# untitled.net
KiCad netlist of a schematic drawn in EAGLE
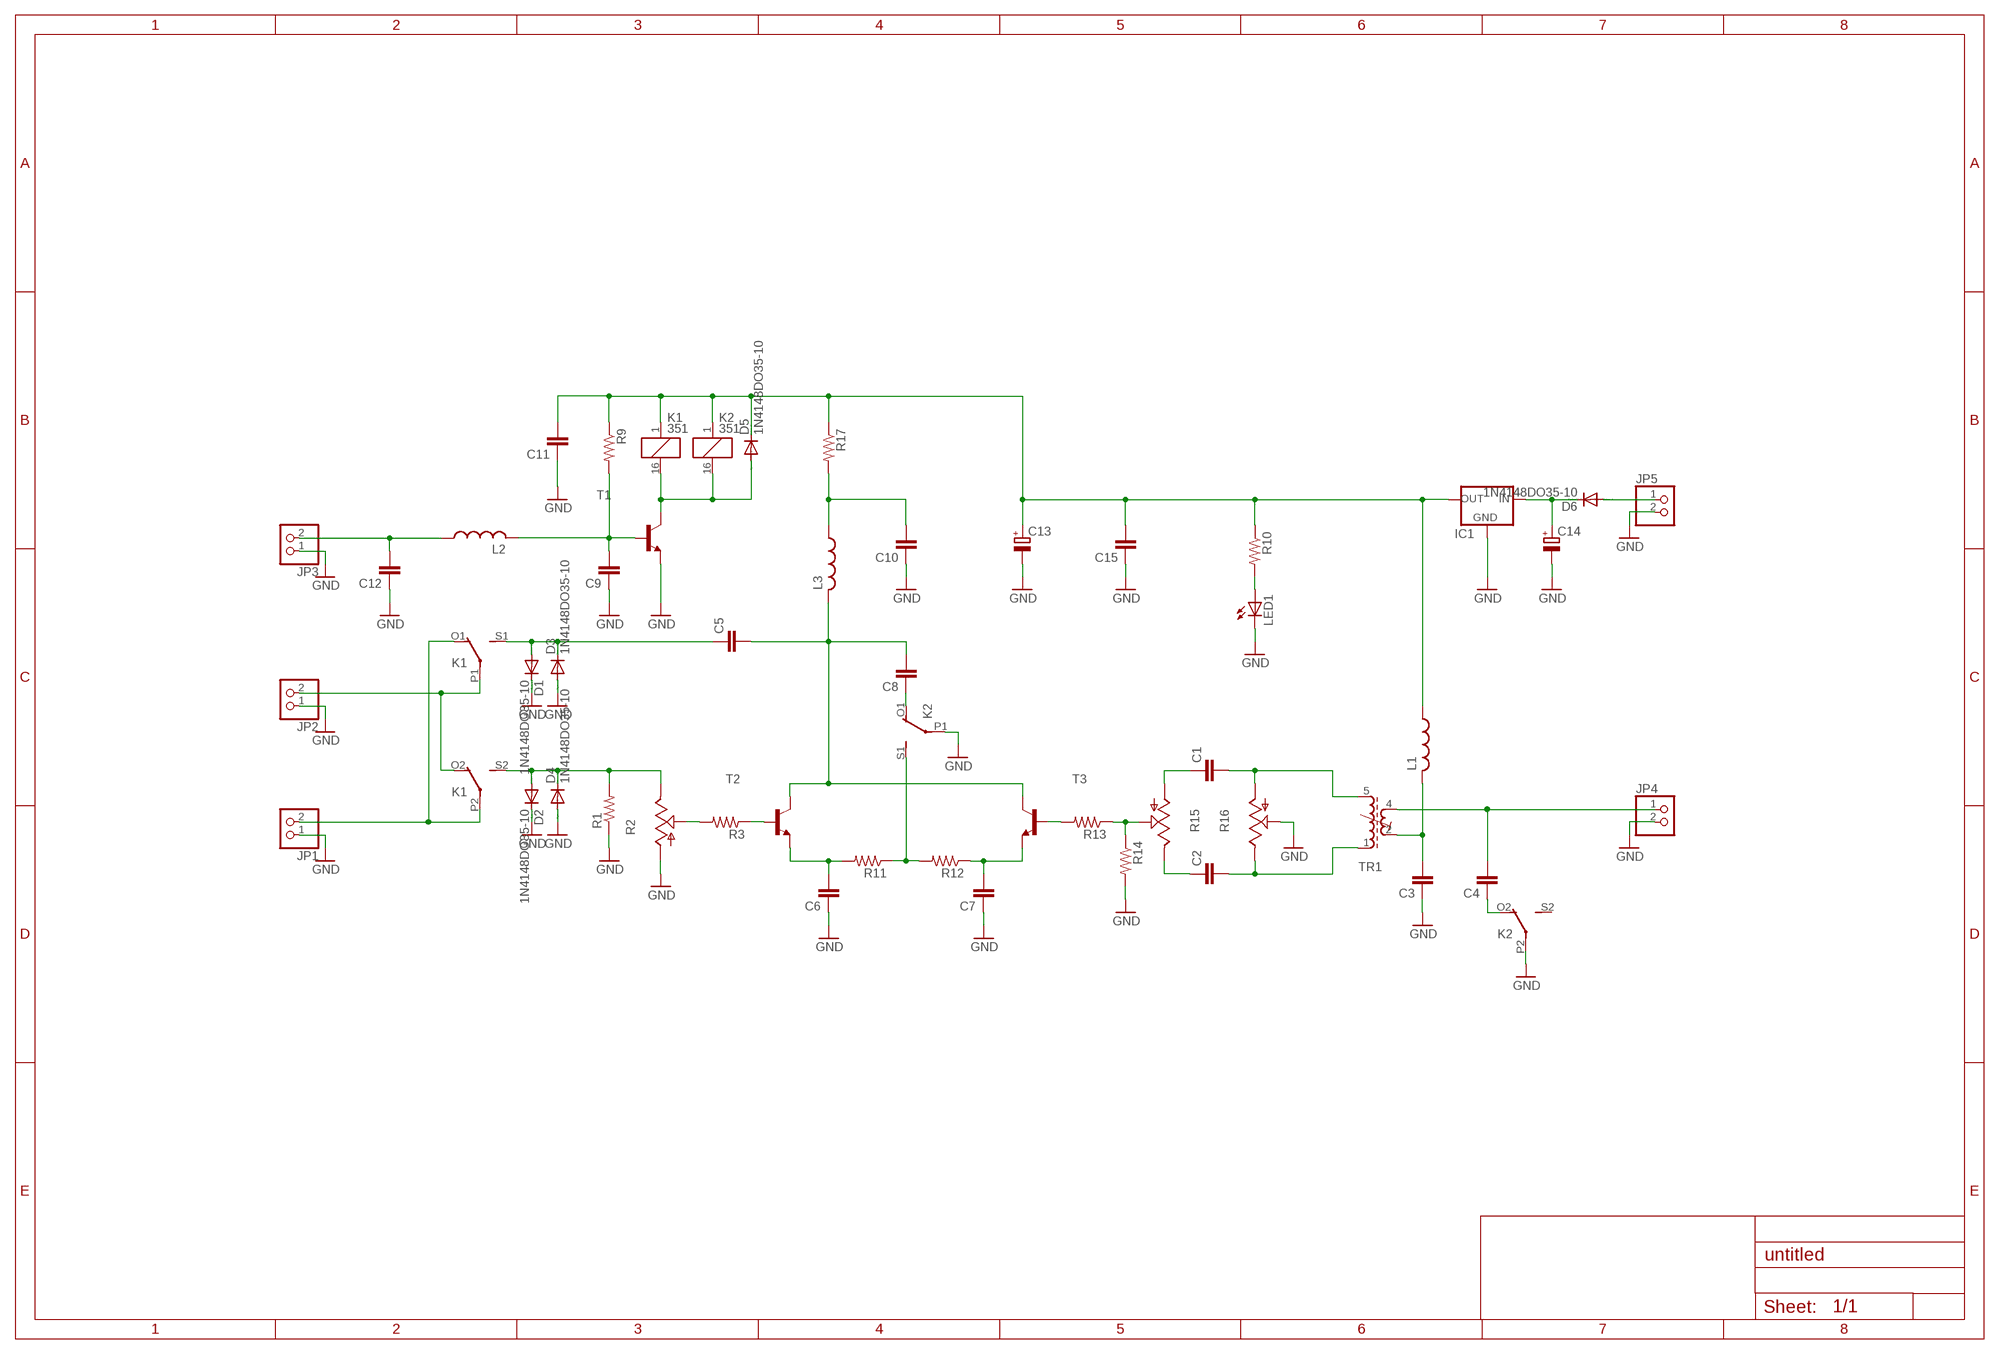
[diagram p0: schematic, sheet 1]

(export (version "E")
  (design (tool "Eeschema 10.0.6"))
  (components
    (comp (ref "C1")
      (value "C-EU050-025X075")
      (footprint "eagle-import:C050-025X075")
      (libsource (lib "eagle-import") (part "C-EU050-025X075"))
    )
    (comp (ref "C2")
      (value "C-EU050-025X075")
      (footprint "eagle-import:C050-025X075")
      (libsource (lib "eagle-import") (part "C-EU050-025X075"))
    )
    (comp (ref "C3")
      (value "C-EU050-025X075")
      (footprint "eagle-import:C050-025X075")
      (libsource (lib "eagle-import") (part "C-EU050-025X075"))
    )
    (comp (ref "C4")
      (value "C-EU050-025X075")
      (footprint "eagle-import:C050-025X075")
      (libsource (lib "eagle-import") (part "C-EU050-025X075"))
    )
    (comp (ref "C5")
      (value "C-EU050-025X075")
      (footprint "eagle-import:C050-025X075")
      (libsource (lib "eagle-import") (part "C-EU050-025X075"))
    )
    (comp (ref "C6")
      (value "C-EU050-025X075")
      (footprint "eagle-import:C050-025X075")
      (libsource (lib "eagle-import") (part "C-EU050-025X075"))
    )
    (comp (ref "C7")
      (value "C-EU050-025X075")
      (footprint "eagle-import:C050-025X075")
      (libsource (lib "eagle-import") (part "C-EU050-025X075"))
    )
    (comp (ref "C8")
      (value "C-EU050-025X075")
      (footprint "eagle-import:C050-025X075")
      (libsource (lib "eagle-import") (part "C-EU050-025X075"))
    )
    (comp (ref "C9")
      (value "C-EU050-025X075")
      (footprint "eagle-import:C050-025X075")
      (libsource (lib "eagle-import") (part "C-EU050-025X075"))
    )
    (comp (ref "C10")
      (value "C-EU050-025X075")
      (footprint "eagle-import:C050-025X075")
      (libsource (lib "eagle-import") (part "C-EU050-025X075"))
    )
    (comp (ref "C11")
      (value "C-EU050-025X075")
      (footprint "eagle-import:C050-025X075")
      (libsource (lib "eagle-import") (part "C-EU050-025X075"))
    )
    (comp (ref "C12")
      (value "C-EU050-025X075")
      (footprint "eagle-import:C050-025X075")
      (libsource (lib "eagle-import") (part "C-EU050-025X075"))
    )
    (comp (ref "C13")
      (value "CPOL-EUE2.5-5")
      (footprint "eagle-import:E2,5-5")
      (libsource (lib "eagle-import") (part "CPOL-EUE2.5-5"))
    )
    (comp (ref "C14")
      (value "CPOL-EUE2.5-5")
      (footprint "eagle-import:E2,5-5")
      (libsource (lib "eagle-import") (part "CPOL-EUE2.5-5"))
    )
    (comp (ref "C15")
      (value "C-EU050-025X075")
      (footprint "eagle-import:C050-025X075")
      (libsource (lib "eagle-import") (part "C-EU050-025X075"))
    )
    (comp (ref "D1")
      (value "1N4148DO35-10")
      (footprint "eagle-import:DO35-10")
      (libsource (lib "eagle-import") (part "1N4148DO35-10"))
    )
    (comp (ref "D2")
      (value "1N4148DO35-10")
      (footprint "eagle-import:DO35-10")
      (libsource (lib "eagle-import") (part "1N4148DO35-10"))
    )
    (comp (ref "D3")
      (value "1N4148DO35-10")
      (footprint "eagle-import:DO35-10")
      (libsource (lib "eagle-import") (part "1N4148DO35-10"))
    )
    (comp (ref "D4")
      (value "1N4148DO35-10")
      (footprint "eagle-import:DO35-10")
      (libsource (lib "eagle-import") (part "1N4148DO35-10"))
    )
    (comp (ref "D5")
      (value "1N4148DO35-10")
      (footprint "eagle-import:DO35-10")
      (libsource (lib "eagle-import") (part "1N4148DO35-10"))
    )
    (comp (ref "D6")
      (value "1N4148DO35-10")
      (footprint "eagle-import:DO35-10")
      (libsource (lib "eagle-import") (part "1N4148DO35-10"))
    )
    (comp (ref "IC1")
      (value "78XXS")
      (footprint "eagle-import:78XXS")
      (libsource (lib "eagle-import") (part "78XXS"))
    )
    (comp (ref "JP1")
      (value "PINHD-1X2")
      (footprint "eagle-import:1X02")
      (libsource (lib "eagle-import") (part "PINHD-1X2"))
    )
    (comp (ref "JP2")
      (value "PINHD-1X2")
      (footprint "eagle-import:1X02")
      (libsource (lib "eagle-import") (part "PINHD-1X2"))
    )
    (comp (ref "JP3")
      (value "PINHD-1X2")
      (footprint "eagle-import:1X02")
      (libsource (lib "eagle-import") (part "PINHD-1X2"))
    )
    (comp (ref "JP4")
      (value "PINHD-1X2")
      (footprint "eagle-import:1X02")
      (libsource (lib "eagle-import") (part "PINHD-1X2"))
    )
    (comp (ref "JP5")
      (value "PINHD-1X2")
      (footprint "eagle-import:1X02")
      (libsource (lib "eagle-import") (part "PINHD-1X2"))
    )
    (comp (ref "K1")
      (value "351")
      (footprint "eagle-import:351")
      (libsource (lib "eagle-import") (part "351"))
    )
    (comp (ref "K2")
      (value "351")
      (footprint "eagle-import:351")
      (libsource (lib "eagle-import") (part "351"))
    )
    (comp (ref "L1")
      (value "L-US0207/7")
      (footprint "eagle-import:0207_7")
      (libsource (lib "eagle-import") (part "L-US0207/7"))
    )
    (comp (ref "L2")
      (value "L-US0207/7")
      (footprint "eagle-import:0207_7")
      (libsource (lib "eagle-import") (part "L-US0207/7"))
    )
    (comp (ref "L3")
      (value "L-US0207/7")
      (footprint "eagle-import:0207_7")
      (libsource (lib "eagle-import") (part "L-US0207/7"))
    )
    (comp (ref "LED1")
      (value "LED3MM")
      (footprint "eagle-import:LED3MM")
      (libsource (lib "eagle-import") (part "LED3MM"))
    )
    (comp (ref "R1")
      (value "R-US_0309/12")
      (footprint "eagle-import:0309_12")
      (libsource (lib "eagle-import") (part "R-US_0309/12"))
    )
    (comp (ref "R2")
      (value "TRIM_US-CIP20C-6MM")
      (footprint "eagle-import:CIP20C-6MM")
      (libsource (lib "eagle-import") (part "TRIM_US-CIP20C-6MM"))
    )
    (comp (ref "R3")
      (value "R-US_0207/7")
      (footprint "eagle-import:0207_7")
      (libsource (lib "eagle-import") (part "R-US_0207/7"))
    )
    (comp (ref "R9")
      (value "R-US_0207/7")
      (footprint "eagle-import:0207_7")
      (libsource (lib "eagle-import") (part "R-US_0207/7"))
    )
    (comp (ref "R10")
      (value "R-US_0207/7")
      (footprint "eagle-import:0207_7")
      (libsource (lib "eagle-import") (part "R-US_0207/7"))
    )
    (comp (ref "R11")
      (value "R-US_0207/7")
      (footprint "eagle-import:0207_7")
      (libsource (lib "eagle-import") (part "R-US_0207/7"))
    )
    (comp (ref "R12")
      (value "R-US_0207/7")
      (footprint "eagle-import:0207_7")
      (libsource (lib "eagle-import") (part "R-US_0207/7"))
    )
    (comp (ref "R13")
      (value "R-US_0207/7")
      (footprint "eagle-import:0207_7")
      (libsource (lib "eagle-import") (part "R-US_0207/7"))
    )
    (comp (ref "R14")
      (value "R-US_0207/7")
      (footprint "eagle-import:0207_7")
      (libsource (lib "eagle-import") (part "R-US_0207/7"))
    )
    (comp (ref "R15")
      (value "TRIM_US-CIP20C-6MM")
      (footprint "eagle-import:CIP20C-6MM")
      (libsource (lib "eagle-import") (part "TRIM_US-CIP20C-6MM"))
    )
    (comp (ref "R16")
      (value "TRIM_US-CIP20C-6MM")
      (footprint "eagle-import:CIP20C-6MM")
      (libsource (lib "eagle-import") (part "TRIM_US-CIP20C-6MM"))
    )
    (comp (ref "R17")
      (value "R-US_0207/7")
      (footprint "eagle-import:0207_7")
      (libsource (lib "eagle-import") (part "R-US_0207/7"))
    )
    (comp (ref "T1")
      (value "-NPN-TO92-EBC")
      (footprint "eagle-import:TO92-EBC")
      (libsource (lib "eagle-import") (part "-NPN-TO92-EBC"))
    )
    (comp (ref "T2")
      (value "-NPN-TO92-EBC")
      (footprint "eagle-import:TO92-EBC")
      (libsource (lib "eagle-import") (part "-NPN-TO92-EBC"))
    )
    (comp (ref "T3")
      (value "-NPN-TO92-EBC")
      (footprint "eagle-import:TO92-EBC")
      (libsource (lib "eagle-import") (part "-NPN-TO92-EBC"))
    )
    (comp (ref "TR1")
      (value "71-4-1524")
      (footprint "eagle-import:71-5")
      (libsource (lib "eagle-import") (part "71-4-1524"))
    )
  )
  (nets
    (net (code "1") (name "GND") (class "Default")
      (node (ref "C10") (pin "1") (pinfunction "1_1") (pintype "passive"))
      (node (ref "C11") (pin "1") (pinfunction "1_1") (pintype "passive"))
      (node (ref "C12") (pin "1") (pinfunction "1_1") (pintype "passive"))
      (node (ref "C13") (pin "-") (pinfunction "-_-") (pintype "passive"))
      (node (ref "C14") (pin "-") (pinfunction "-_-") (pintype "passive"))
      (node (ref "C15") (pin "1") (pinfunction "1_1") (pintype "passive"))
      (node (ref "C3") (pin "1") (pinfunction "1_1") (pintype "passive"))
      (node (ref "C6") (pin "1") (pinfunction "1_1") (pintype "passive"))
      (node (ref "C7") (pin "1") (pinfunction "1_1") (pintype "passive"))
      (node (ref "C9") (pin "1") (pinfunction "1_1") (pintype "passive"))
      (node (ref "D1") (pin "C") (pinfunction "C_C") (pintype "passive"))
      (node (ref "D2") (pin "C") (pinfunction "C_C") (pintype "passive"))
      (node (ref "D3") (pin "A") (pinfunction "A_A") (pintype "passive"))
      (node (ref "D4") (pin "A") (pinfunction "A_A") (pintype "passive"))
      (node (ref "IC1") (pin "GND") (pinfunction "GND_GND") (pintype "input"))
      (node (ref "JP1") (pin "1") (pinfunction "1_1") (pintype "passive"))
      (node (ref "JP2") (pin "1") (pinfunction "1_1") (pintype "passive"))
      (node (ref "JP3") (pin "1") (pinfunction "1_1") (pintype "passive"))
      (node (ref "JP4") (pin "2") (pinfunction "2_2") (pintype "passive"))
      (node (ref "JP5") (pin "2") (pinfunction "2_2") (pintype "passive"))
      (node (ref "K2") (pin "P1") (pinfunction "P_P1") (pintype "passive"))
      (node (ref "K2") (pin "P2") (pinfunction "P_P2") (pintype "passive"))
      (node (ref "LED1") (pin "K") (pinfunction "C_K") (pintype "passive"))
      (node (ref "R1") (pin "1") (pinfunction "1_1") (pintype "passive"))
      (node (ref "R14") (pin "2") (pinfunction "2_2") (pintype "passive"))
      (node (ref "R16") (pin "S") (pinfunction "S_S") (pintype "passive"))
      (node (ref "R2") (pin "A") (pinfunction "A_A") (pintype "passive"))
      (node (ref "T1") (pin "E") (pinfunction "E_E") (pintype "passive"))
    )
    (net (code "2") (name "Net-(C1-Pad1)") (class "Default")
      (node (ref "C1") (pin "1") (pinfunction "1_1") (pintype "passive"))
      (node (ref "R15") (pin "A") (pinfunction "A_A") (pintype "passive"))
    )
    (net (code "3") (name "Net-(C2-Pad1)") (class "Default")
      (node (ref "C2") (pin "1") (pinfunction "1_1") (pintype "passive"))
      (node (ref "R15") (pin "E") (pinfunction "E_E") (pintype "passive"))
    )
    (net (code "4") (name "Net-(C5-Pad2)") (class "Default")
      (node (ref "C5") (pin "2") (pinfunction "2_2") (pintype "passive"))
      (node (ref "C8") (pin "2") (pinfunction "2_2") (pintype "passive"))
      (node (ref "L3") (pin "2") (pinfunction "2_2") (pintype "passive"))
      (node (ref "T2") (pin "C") (pinfunction "C_C") (pintype "passive"))
      (node (ref "T3") (pin "C") (pinfunction "C_C") (pintype "passive"))
    )
    (net (code "5") (name "Net-(C6-Pad2)") (class "Default")
      (node (ref "C6") (pin "2") (pinfunction "2_2") (pintype "passive"))
      (node (ref "R11") (pin "2") (pinfunction "2_2") (pintype "passive"))
      (node (ref "T2") (pin "E") (pinfunction "E_E") (pintype "passive"))
    )
    (net (code "6") (name "Net-(C7-Pad2)") (class "Default")
      (node (ref "C7") (pin "2") (pinfunction "2_2") (pintype "passive"))
      (node (ref "R12") (pin "1") (pinfunction "1_1") (pintype "passive"))
      (node (ref "T3") (pin "E") (pinfunction "E_E") (pintype "passive"))
    )
    (net (code "7") (name "Net-(C9-Pad2)") (class "Default")
      (node (ref "C9") (pin "2") (pinfunction "2_2") (pintype "passive"))
      (node (ref "L2") (pin "2") (pinfunction "2_2") (pintype "passive"))
      (node (ref "R9") (pin "2") (pinfunction "2_2") (pintype "passive"))
      (node (ref "T1") (pin "B") (pinfunction "B_B") (pintype "passive"))
    )
    (net (code "8") (name "Net-(C10-Pad2)") (class "Default")
      (node (ref "C10") (pin "2") (pinfunction "2_2") (pintype "passive"))
      (node (ref "L3") (pin "1") (pinfunction "1_1") (pintype "passive"))
      (node (ref "R17") (pin "2") (pinfunction "2_2") (pintype "passive"))
    )
    (net (code "9") (name "Net-(C11-Pad2)") (class "Default")
      (node (ref "C11") (pin "2") (pinfunction "2_2") (pintype "passive"))
      (node (ref "C13") (pin "+") (pinfunction "+_+") (pintype "passive"))
      (node (ref "C15") (pin "2") (pinfunction "2_2") (pintype "passive"))
      (node (ref "D5") (pin "C") (pinfunction "C_C") (pintype "passive"))
      (node (ref "IC1") (pin "OUT") (pinfunction "OUT_OUT") (pintype "passive"))
      (node (ref "K1") (pin "1") (pinfunction "1_1") (pintype "passive"))
      (node (ref "K2") (pin "1") (pinfunction "1_1") (pintype "passive"))
      (node (ref "L1") (pin "1") (pinfunction "1_1") (pintype "passive"))
      (node (ref "R10") (pin "1") (pinfunction "1_1") (pintype "passive"))
      (node (ref "R17") (pin "1") (pinfunction "1_1") (pintype "passive"))
      (node (ref "R9") (pin "1") (pinfunction "1_1") (pintype "passive"))
    )
    (net (code "10") (name "Net-(C12-Pad2)") (class "Default")
      (node (ref "C12") (pin "2") (pinfunction "2_2") (pintype "passive"))
      (node (ref "JP3") (pin "2") (pinfunction "2_2") (pintype "passive"))
      (node (ref "L2") (pin "1") (pinfunction "1_1") (pintype "passive"))
    )
    (net (code "11") (name "Net-(C14-Pad+)") (class "Default")
      (node (ref "C14") (pin "+") (pinfunction "+_+") (pintype "passive"))
      (node (ref "D6") (pin "C") (pinfunction "C_C") (pintype "passive"))
      (node (ref "IC1") (pin "IN") (pinfunction "IN_IN") (pintype "input"))
    )
    (net (code "12") (name "Net-(D6-PadA)") (class "Default")
      (node (ref "D6") (pin "A") (pinfunction "A_A") (pintype "passive"))
      (node (ref "JP5") (pin "1") (pinfunction "1_1") (pintype "passive"))
    )
    (net (code "13") (name "Net-(K1A-2)") (class "Default")
      (node (ref "D5") (pin "A") (pinfunction "A_A") (pintype "passive"))
      (node (ref "K1") (pin "16") (pinfunction "2_16") (pintype "passive"))
      (node (ref "K2") (pin "16") (pinfunction "2_16") (pintype "passive"))
      (node (ref "T1") (pin "C") (pinfunction "C_C") (pintype "passive"))
    )
    (net (code "14") (name "Net-(K1B-O)") (class "Default")
      (node (ref "JP1") (pin "2") (pinfunction "2_2") (pintype "passive"))
      (node (ref "K1") (pin "O1") (pinfunction "O_O1") (pintype "passive"))
      (node (ref "K1") (pin "P2") (pinfunction "P_P2") (pintype "passive"))
    )
    (net (code "15") (name "Net-(K1B-P)") (class "Default")
      (node (ref "JP2") (pin "2") (pinfunction "2_2") (pintype "passive"))
      (node (ref "K1") (pin "O2") (pinfunction "O_O2") (pintype "passive"))
      (node (ref "K1") (pin "P1") (pinfunction "P_P1") (pintype "passive"))
    )
    (net (code "16") (name "Net-(K1B-S)") (class "Default")
      (node (ref "C5") (pin "1") (pinfunction "1_1") (pintype "passive"))
      (node (ref "D1") (pin "A") (pinfunction "A_A") (pintype "passive"))
      (node (ref "D3") (pin "C") (pinfunction "C_C") (pintype "passive"))
      (node (ref "K1") (pin "S1") (pinfunction "S_S1") (pintype "passive"))
    )
    (net (code "17") (name "Net-(K1C-S)") (class "Default")
      (node (ref "D2") (pin "A") (pinfunction "A_A") (pintype "passive"))
      (node (ref "D4") (pin "C") (pinfunction "C_C") (pintype "passive"))
      (node (ref "K1") (pin "S2") (pinfunction "S_S2") (pintype "passive"))
      (node (ref "R1") (pin "2") (pinfunction "2_2") (pintype "passive"))
      (node (ref "R2") (pin "E") (pinfunction "E_E") (pintype "passive"))
    )
    (net (code "18") (name "Net-(K2B-O)") (class "Default")
      (node (ref "C8") (pin "1") (pinfunction "1_1") (pintype "passive"))
      (node (ref "K2") (pin "O1") (pinfunction "O_O1") (pintype "passive"))
    )
    (net (code "19") (name "Net-(K2B-S)") (class "Default")
      (node (ref "K2") (pin "S1") (pinfunction "S_S1") (pintype "passive"))
      (node (ref "R11") (pin "1") (pinfunction "1_1") (pintype "passive"))
      (node (ref "R12") (pin "2") (pinfunction "2_2") (pintype "passive"))
    )
    (net (code "20") (name "Net-(K2C-O)") (class "Default")
      (node (ref "C4") (pin "1") (pinfunction "1_1") (pintype "passive"))
      (node (ref "K2") (pin "O2") (pinfunction "O_O2") (pintype "passive"))
    )
    (net (code "21") (name "Net-(LED1-PadA)") (class "Default")
      (node (ref "LED1") (pin "A") (pinfunction "A_A") (pintype "passive"))
      (node (ref "R10") (pin "2") (pinfunction "2_2") (pintype "passive"))
    )
    (net (code "22") (name "Net-(R2-PadS)") (class "Default")
      (node (ref "R2") (pin "S") (pinfunction "S_S") (pintype "passive"))
      (node (ref "R3") (pin "2") (pinfunction "2_2") (pintype "passive"))
    )
    (net (code "23") (name "Net-(R3-Pad1)") (class "Default")
      (node (ref "R3") (pin "1") (pinfunction "1_1") (pintype "passive"))
      (node (ref "T2") (pin "B") (pinfunction "B_B") (pintype "passive"))
    )
    (net (code "24") (name "Net-(R13-Pad1)") (class "Default")
      (node (ref "R13") (pin "1") (pinfunction "1_1") (pintype "passive"))
      (node (ref "R14") (pin "1") (pinfunction "1_1") (pintype "passive"))
      (node (ref "R15") (pin "S") (pinfunction "S_S") (pintype "passive"))
    )
    (net (code "25") (name "Net-(R13-Pad2)") (class "Default")
      (node (ref "R13") (pin "2") (pinfunction "2_2") (pintype "passive"))
      (node (ref "T3") (pin "B") (pinfunction "B_B") (pintype "passive"))
    )
    (net (code "26") (name "Net-(TR1A-A1)") (class "Default")
      (node (ref "C2") (pin "2") (pinfunction "2_2") (pintype "passive"))
      (node (ref "R16") (pin "E") (pinfunction "E_E") (pintype "passive"))
      (node (ref "TR1") (pin "1") (pinfunction "A1_1") (pintype "passive"))
    )
    (net (code "27") (name "Net-(TR1A-A2)") (class "Default")
      (node (ref "C3") (pin "2") (pinfunction "2_2") (pintype "passive"))
      (node (ref "L1") (pin "2") (pinfunction "2_2") (pintype "passive"))
      (node (ref "TR1") (pin "2") (pinfunction "A2_2") (pintype "passive"))
    )
    (net (code "28") (name "Net-(TR1A-E1)") (class "Default")
      (node (ref "C1") (pin "2") (pinfunction "2_2") (pintype "passive"))
      (node (ref "R16") (pin "A") (pinfunction "A_A") (pintype "passive"))
      (node (ref "TR1") (pin "5") (pinfunction "E1_5") (pintype "passive"))
    )
    (net (code "29") (name "Net-(TR1A-E2)") (class "Default")
      (node (ref "C4") (pin "2") (pinfunction "2_2") (pintype "passive"))
      (node (ref "JP4") (pin "1") (pinfunction "1_1") (pintype "passive"))
      (node (ref "TR1") (pin "4") (pinfunction "E2_4") (pintype "passive"))
    )
    (net (code "30") (name "unconnected-(K2C-S-PadS2)") (class "Default")
      (node (ref "K2") (pin "S2") (pinfunction "S_S2") (pintype "passive"))
    )
  )
)
